# tinyCore.net
KiCad netlist of a schematic drawn in Altium Designer
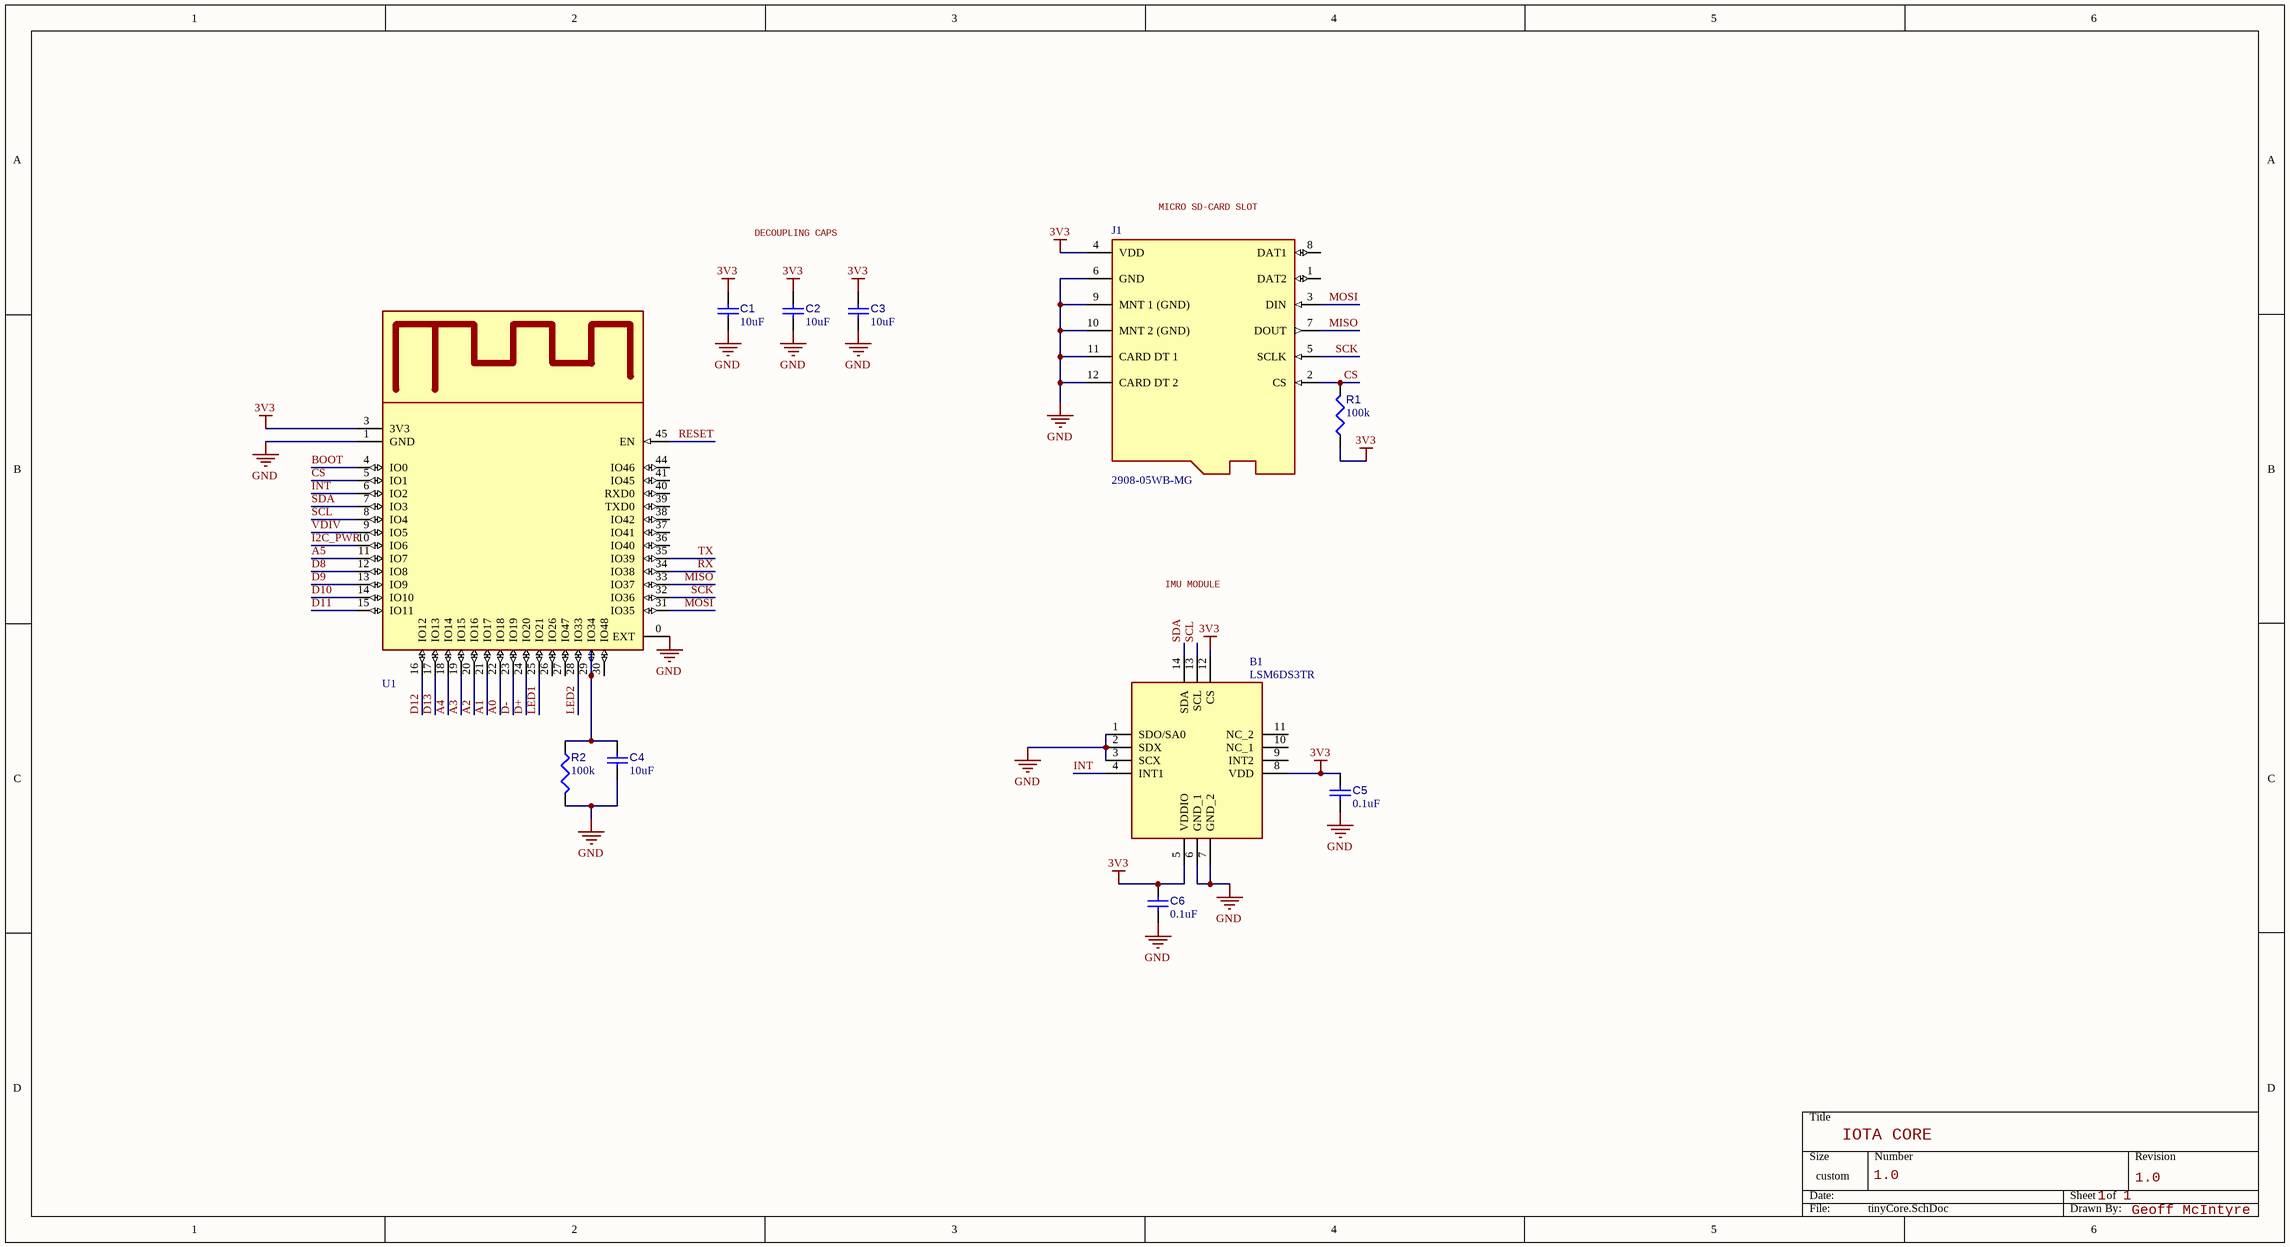
[diagram p0: tinyCore.SchDoc]

(export (version "E")
  (design (tool "Eeschema 10.0.6"))
  (components
    (comp (ref "B1")
      (value "LSM6DS3TR")
      (footprint "LSM6DS3TR")
      (description "DFD PROTECTION & FILTER")
      (fields (field (name "MOUSER PART NUMBER") "511-LSM6DS3TR"))
      (libsource (lib "McIntyre Industries") (part "LSM6DS3TR"))
    )
    (comp (ref "C1")
      (value "10uF")
      (footprint "CAPC1608X87X35NL15T15")
      (description "Chip Capacitor, 10 uF, +/- 0.25 uF, 50 V, 0603 (1608 Metric)")
      (fields
        (field (name "TOLERANCE") "0.25%")
        (field (name "Comment") "Capacitor 10 uF +/- 0.25 uF 50 V 0603")
      )
      (libsource (lib "Prototypical Design") (part "CAP-NP-2"))
    )
    (comp (ref "C2")
      (value "10uF")
      (footprint "CAPC1608X87X35NL15T15")
      (description "Chip Capacitor, 10 uF, +/- 0.25 uF, 50 V, 0603 (1608 Metric)")
      (fields
        (field (name "TOLERANCE") "0.25%")
        (field (name "Comment") "Capacitor 10 uF +/- 0.25 uF 50 V 0603")
      )
      (libsource (lib "Prototypical Design") (part "CAP-NP-2"))
    )
    (comp (ref "C3")
      (value "10uF")
      (footprint "CAPC1608X87X35NL15T15")
      (description "Chip Capacitor, 10 uF, +/- 0.25 uF, 50 V, 0603 (1608 Metric)")
      (fields
        (field (name "TOLERANCE") "0.25%")
        (field (name "Comment") "Capacitor 10 uF +/- 0.25 uF 50 V 0603")
      )
      (libsource (lib "Prototypical Design") (part "CAP-NP-2"))
    )
    (comp (ref "C4")
      (value "10uF")
      (footprint "CAPC1608X87X35NL15T15")
      (description "Chip Capacitor, 10 uF, +/- 0.25 uF, 50 V, 0603 (1608 Metric)")
      (fields
        (field (name "TOLERANCE") "0.25%")
        (field (name "Comment") "Capacitor 10 uF +/- 0.25 uF 50 V 0603")
      )
      (libsource (lib "Prototypical Design") (part "CAP-NP-2"))
    )
    (comp (ref "C5")
      (value "0.1uF")
      (footprint "CAPC1608X87X35NL15T15")
      (description "Chip Capacitor, 0.1 uF, +/- 0.25 pF, 50 V, 0603 (1608 Metric)")
      (fields (field (name "TOLERANCE") "0.25%") (field (name "Comment") "Capacitor  0.1 uF 50 V 0603"))
      (libsource (lib "Prototypical Design") (part "CAP-NP-2"))
    )
    (comp (ref "C6")
      (value "0.1uF")
      (footprint "CAPC1608X87X35NL15T15")
      (description "Chip Capacitor, 0.1 uF, +/- 0.25 pF, 50 V, 0603 (1608 Metric)")
      (fields (field (name "TOLERANCE") "0.25%") (field (name "Comment") "Capacitor  0.1 uF 50 V 0603"))
      (libsource (lib "Prototypical Design") (part "CAP-NP-2"))
    )
    (comp (ref "J1")
      (value "2908-05WB-MG")
      (footprint "FP-2908-05WB-MG-MFG")
      (description "CONN MICRO SD CARD PUSH-PUSH R/A")
      (libsource (lib "altium-import") (part "root_0_fda8729df53732acfd28ea6eb69392a_"))
    )
    (comp (ref "R1")
      (value "100k")
      (footprint "RESC1608X55X25ML10T15")
      (description "Chip Resistor, 100 KOhm, +/- 1%, 0.1 W, -55 to 155 degC, 0603 (1608 Metric)")
      (fields (field (name "TOLERANCE") "1%") (field (name "POWER") "100mW"))
      (libsource (lib "Prototypical Design") (part "RES-2"))
    )
    (comp (ref "R2")
      (value "100k")
      (footprint "RESC1608X55X25ML10T15")
      (description "Chip Resistor, 100 KOhm, +/- 1%, 0.1 W, -55 to 155 degC, 0603 (1608 Metric)")
      (fields (field (name "TOLERANCE") "1%") (field (name "POWER") "100mW"))
      (libsource (lib "Prototypical Design") (part "RES-2"))
    )
    (comp (ref "U1")
      (value "ESP32-S3-MINI-1-N8")
      (footprint "ESP32-S3-MINI-1-N8")
      (description "SMD module, ESP32-S3FN8, 8 MB SPI flash, PCB antenna")
      (fields
        (field (name "DIGIKEY PART NUMBER") "1965-ESP32-S3-MINI-1-N8CT-ND")
        (field (name "MANUFACTURER") "Espressif Systems")
      )
      (libsource (lib "Mister Industries") (part "ESP32-S3-MINI-1-N8"))
    )
  )
  (nets
    (net (code "2") (name "/A0") (class "Default")
      (node (ref "U1") (pin "22") (pinfunction "IO18_22") (pintype "bidirectional"))
    )
    (net (code "3") (name "/A1") (class "Default")
      (node (ref "U1") (pin "21") (pinfunction "IO17_21") (pintype "bidirectional"))
    )
    (net (code "4") (name "/A2") (class "Default")
      (node (ref "U1") (pin "20") (pinfunction "IO16_20") (pintype "bidirectional"))
    )
    (net (code "5") (name "/A3") (class "Default")
      (node (ref "U1") (pin "19") (pinfunction "IO15_19") (pintype "bidirectional"))
    )
    (net (code "6") (name "/A4") (class "Default")
      (node (ref "U1") (pin "18") (pinfunction "IO14_18") (pintype "bidirectional"))
    )
    (net (code "7") (name "/A5") (class "Default")
      (node (ref "U1") (pin "11") (pinfunction "IO7_11") (pintype "bidirectional"))
    )
    (net (code "8") (name "/BOOT") (class "Default")
      (node (ref "U1") (pin "4") (pinfunction "IO0_4") (pintype "bidirectional"))
    )
    (net (code "9") (name "/CS") (class "Default")
      (node (ref "J1") (pin "2") (pinfunction "CS_2") (pintype "input"))
      (node (ref "R1") (pin "2") (pinfunction "2_2") (pintype "passive"))
      (node (ref "U1") (pin "5") (pinfunction "IO1_5") (pintype "bidirectional"))
    )
    (net (code "10") (name "/D+") (class "Default")
      (node (ref "U1") (pin "24") (pinfunction "IO20_24") (pintype "bidirectional"))
    )
    (net (code "11") (name "/D-") (class "Default")
      (node (ref "U1") (pin "23") (pinfunction "IO19_23") (pintype "bidirectional"))
    )
    (net (code "12") (name "/D8") (class "Default")
      (node (ref "U1") (pin "12") (pinfunction "IO8_12") (pintype "bidirectional"))
    )
    (net (code "13") (name "/D9") (class "Default")
      (node (ref "U1") (pin "13") (pinfunction "IO9_13") (pintype "bidirectional"))
    )
    (net (code "14") (name "/D10") (class "Default")
      (node (ref "U1") (pin "14") (pinfunction "IO10_14") (pintype "bidirectional"))
    )
    (net (code "15") (name "/D11") (class "Default")
      (node (ref "U1") (pin "15") (pinfunction "IO11_15") (pintype "bidirectional"))
    )
    (net (code "16") (name "/D12") (class "Default")
      (node (ref "U1") (pin "16") (pinfunction "IO12_16") (pintype "bidirectional"))
    )
    (net (code "17") (name "/D13") (class "Default")
      (node (ref "U1") (pin "17") (pinfunction "IO13_17") (pintype "bidirectional"))
    )
    (net (code "18") (name "/I2C_PWR") (class "Default")
      (node (ref "U1") (pin "10") (pinfunction "IO6_10") (pintype "bidirectional"))
    )
    (net (code "19") (name "/INT") (class "Default")
      (node (ref "B1") (pin "4") (pinfunction "INT1_4") (pintype "passive"))
      (node (ref "U1") (pin "6") (pinfunction "IO2_6") (pintype "bidirectional"))
    )
    (net (code "20") (name "/LED1") (class "Default")
      (node (ref "U1") (pin "25") (pinfunction "IO21_25") (pintype "bidirectional"))
    )
    (net (code "21") (name "/LED2") (class "Default")
      (node (ref "U1") (pin "28") (pinfunction "IO33_28") (pintype "bidirectional"))
    )
    (net (code "22") (name "/MISO") (class "Default")
      (node (ref "J1") (pin "7") (pinfunction "DOUT_7") (pintype "output"))
      (node (ref "U1") (pin "33") (pinfunction "IO37_33") (pintype "bidirectional"))
    )
    (net (code "23") (name "/MOSI") (class "Default")
      (node (ref "J1") (pin "3") (pinfunction "DIN_3") (pintype "input"))
      (node (ref "U1") (pin "31") (pinfunction "IO35_31") (pintype "bidirectional"))
    )
    (net (code "24") (name "/RESET") (class "Default")
      (node (ref "U1") (pin "45") (pinfunction "EN_45") (pintype "input"))
    )
    (net (code "25") (name "/RX") (class "Default")
      (node (ref "U1") (pin "34") (pinfunction "IO38_34") (pintype "bidirectional"))
    )
    (net (code "26") (name "/SCK") (class "Default")
      (node (ref "J1") (pin "5") (pinfunction "SCLK_5") (pintype "input"))
      (node (ref "U1") (pin "32") (pinfunction "IO36_32") (pintype "bidirectional"))
    )
    (net (code "27") (name "/SCL") (class "Default")
      (node (ref "B1") (pin "13") (pinfunction "SCL_13") (pintype "passive"))
      (node (ref "U1") (pin "8") (pinfunction "IO4_8") (pintype "bidirectional"))
    )
    (net (code "28") (name "/SDA") (class "Default")
      (node (ref "B1") (pin "14") (pinfunction "SDA_14") (pintype "passive"))
      (node (ref "U1") (pin "7") (pinfunction "IO3_7") (pintype "bidirectional"))
    )
    (net (code "29") (name "/TX") (class "Default")
      (node (ref "U1") (pin "35") (pinfunction "IO39_35") (pintype "bidirectional"))
    )
    (net (code "30") (name "/VDIV") (class "Default")
      (node (ref "U1") (pin "9") (pinfunction "IO5_9") (pintype "bidirectional"))
    )
    (net (code "31") (name "3V3") (class "Default")
      (node (ref "B1") (pin "12") (pinfunction "CS_12") (pintype "passive"))
      (node (ref "B1") (pin "5") (pinfunction "VDDIO_5") (pintype "passive"))
      (node (ref "B1") (pin "8") (pinfunction "VDD_8") (pintype "passive"))
      (node (ref "C1") (pin "2") (pinfunction "2_2") (pintype "passive"))
      (node (ref "C2") (pin "2") (pinfunction "2_2") (pintype "passive"))
      (node (ref "C3") (pin "2") (pinfunction "2_2") (pintype "passive"))
      (node (ref "C5") (pin "2") (pinfunction "2_2") (pintype "passive"))
      (node (ref "C6") (pin "2") (pinfunction "2_2") (pintype "passive"))
      (node (ref "J1") (pin "4") (pinfunction "VDD_4") (pintype "passive"))
      (node (ref "R1") (pin "1") (pinfunction "1_1") (pintype "passive"))
      (node (ref "U1") (pin "3") (pinfunction "3V3_3") (pintype "power_in"))
    )
    (net (code "32") (name "GND") (class "Default")
      (node (ref "B1") (pin "1") (pinfunction "SDO/SA0_1") (pintype "passive"))
      (node (ref "B1") (pin "2") (pinfunction "SDX_2") (pintype "passive"))
      (node (ref "B1") (pin "3") (pinfunction "SCX_3") (pintype "passive"))
      (node (ref "B1") (pin "6") (pinfunction "GND_1_6") (pintype "passive"))
      (node (ref "B1") (pin "7") (pinfunction "GND_2_7") (pintype "passive"))
      (node (ref "C1") (pin "1") (pinfunction "1_1") (pintype "passive"))
      (node (ref "C2") (pin "1") (pinfunction "1_1") (pintype "passive"))
      (node (ref "C3") (pin "1") (pinfunction "1_1") (pintype "passive"))
      (node (ref "C4") (pin "1") (pinfunction "1_1") (pintype "passive"))
      (node (ref "C5") (pin "1") (pinfunction "1_1") (pintype "passive"))
      (node (ref "C6") (pin "1") (pinfunction "1_1") (pintype "passive"))
      (node (ref "J1") (pin "10") (pinfunction "MNT_2_(GND)_10") (pintype "passive"))
      (node (ref "J1") (pin "11") (pinfunction "CARD_DT_1_11") (pintype "passive"))
      (node (ref "J1") (pin "12") (pinfunction "CARD_DT_2_12") (pintype "passive"))
      (node (ref "J1") (pin "6") (pinfunction "GND_6") (pintype "passive"))
      (node (ref "J1") (pin "9") (pinfunction "MNT_1_(GND)_9") (pintype "passive"))
      (node (ref "R2") (pin "2") (pinfunction "2_2") (pintype "passive"))
      (node (ref "U1") (pin "0") (pinfunction "EXT_0") (pintype "power_in"))
      (node (ref "U1") (pin "1") (pinfunction "GND_1") (pintype "power_in"))
    )
    (net (code "33") (name "Net-(U1-IO34)") (class "Default")
      (node (ref "C4") (pin "2") (pinfunction "2_2") (pintype "passive"))
      (node (ref "R2") (pin "1") (pinfunction "1_1") (pintype "passive"))
      (node (ref "U1") (pin "29") (pinfunction "IO34_29") (pintype "bidirectional"))
    )
    (net (code "34") (name "unconnected-(B1-INT2-Pad9)") (class "Default")
      (node (ref "B1") (pin "9") (pinfunction "INT2_9") (pintype "passive"))
    )
    (net (code "35") (name "unconnected-(B1-NC_1-Pad10)") (class "Default")
      (node (ref "B1") (pin "10") (pinfunction "NC_1_10") (pintype "passive"))
    )
    (net (code "36") (name "unconnected-(B1-NC_2-Pad11)") (class "Default")
      (node (ref "B1") (pin "11") (pinfunction "NC_2_11") (pintype "passive"))
    )
    (net (code "37") (name "unconnected-(J1-DAT1-Pad8)") (class "Default")
      (node (ref "J1") (pin "8") (pinfunction "DAT1_8") (pintype "bidirectional"))
    )
    (net (code "38") (name "unconnected-(J1-DAT2-Pad1)") (class "Default")
      (node (ref "J1") (pin "1") (pinfunction "DAT2_1") (pintype "bidirectional"))
    )
    (net (code "39") (name "unconnected-(U1-IO26-Pad26)") (class "Default")
      (node (ref "U1") (pin "26") (pinfunction "IO26_26") (pintype "bidirectional"))
    )
    (net (code "40") (name "unconnected-(U1-IO40-Pad36)") (class "Default")
      (node (ref "U1") (pin "36") (pinfunction "IO40_36") (pintype "bidirectional"))
    )
    (net (code "41") (name "unconnected-(U1-IO41-Pad37)") (class "Default")
      (node (ref "U1") (pin "37") (pinfunction "IO41_37") (pintype "bidirectional"))
    )
    (net (code "42") (name "unconnected-(U1-IO42-Pad38)") (class "Default")
      (node (ref "U1") (pin "38") (pinfunction "IO42_38") (pintype "bidirectional"))
    )
    (net (code "43") (name "unconnected-(U1-IO45-Pad41)") (class "Default")
      (node (ref "U1") (pin "41") (pinfunction "IO45_41") (pintype "bidirectional"))
    )
    (net (code "44") (name "unconnected-(U1-IO46-Pad44)") (class "Default")
      (node (ref "U1") (pin "44") (pinfunction "IO46_44") (pintype "bidirectional"))
    )
    (net (code "45") (name "unconnected-(U1-IO47-Pad27)") (class "Default")
      (node (ref "U1") (pin "27") (pinfunction "IO47_27") (pintype "bidirectional"))
    )
    (net (code "46") (name "unconnected-(U1-IO48-Pad30)") (class "Default")
      (node (ref "U1") (pin "30") (pinfunction "IO48_30") (pintype "bidirectional"))
    )
    (net (code "47") (name "unconnected-(U1-RXD0-Pad40)") (class "Default")
      (node (ref "U1") (pin "40") (pinfunction "RXD0_40") (pintype "bidirectional"))
    )
    (net (code "48") (name "unconnected-(U1-TXD0-Pad39)") (class "Default")
      (node (ref "U1") (pin "39") (pinfunction "TXD0_39") (pintype "bidirectional"))
    )
  )
)
